# Main.net
KiCad netlist of a schematic drawn in Altium Designer
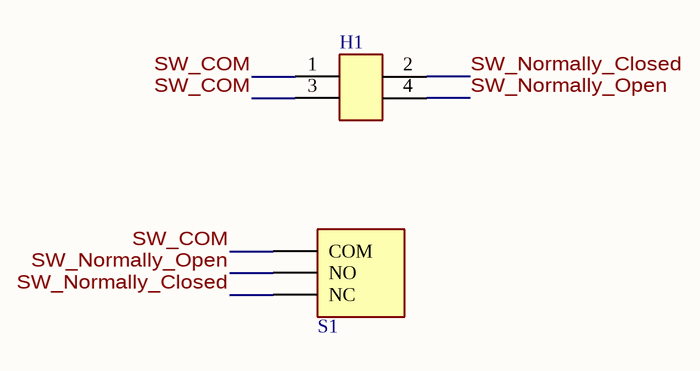
[diagram p0: Main.SchDoc]

(export (version "E")
  (design (tool "Eeschema 10.0.6"))
  (components
    (comp (ref "H1")
      (value "[Header] 2x2 90deg Male")
      (footprint "[Header] 2x2 90deg Male")
      (description "PH2RA-04-UA")
      (libsource (lib "Connectors") (part "[Header] 2x2 90deg Male"))
    )
    (comp (ref "S1")
      (value "[SPDT] Limit Switch w/ Roller")
      (footprint "[SPDT] Limit Switch w/ Roller")
      (libsource (lib "Switches") (part "[SPDT] Limit Switch w/ Roller"))
    )
  )
  (nets
    (net (code "1") (name "/SW_COM") (class "Default")
      (node (ref "H1") (pin "1") (pintype "passive"))
      (node (ref "H1") (pin "3") (pintype "passive"))
      (node (ref "S1") (pin "1") (pinfunction "COM_1") (pintype "power_in"))
    )
    (net (code "2") (name "/SW_Normally_Closed") (class "Default")
      (node (ref "H1") (pin "2") (pintype "passive"))
      (node (ref "S1") (pin "3") (pinfunction "NC_3") (pintype "power_in"))
    )
    (net (code "3") (name "/SW_Normally_Open") (class "Default")
      (node (ref "H1") (pin "4") (pintype "passive"))
      (node (ref "S1") (pin "2") (pinfunction "NO_2") (pintype "power_in"))
    )
  )
)
